# led_controller.net
KiCad netlist of a schematic drawn in EAGLE
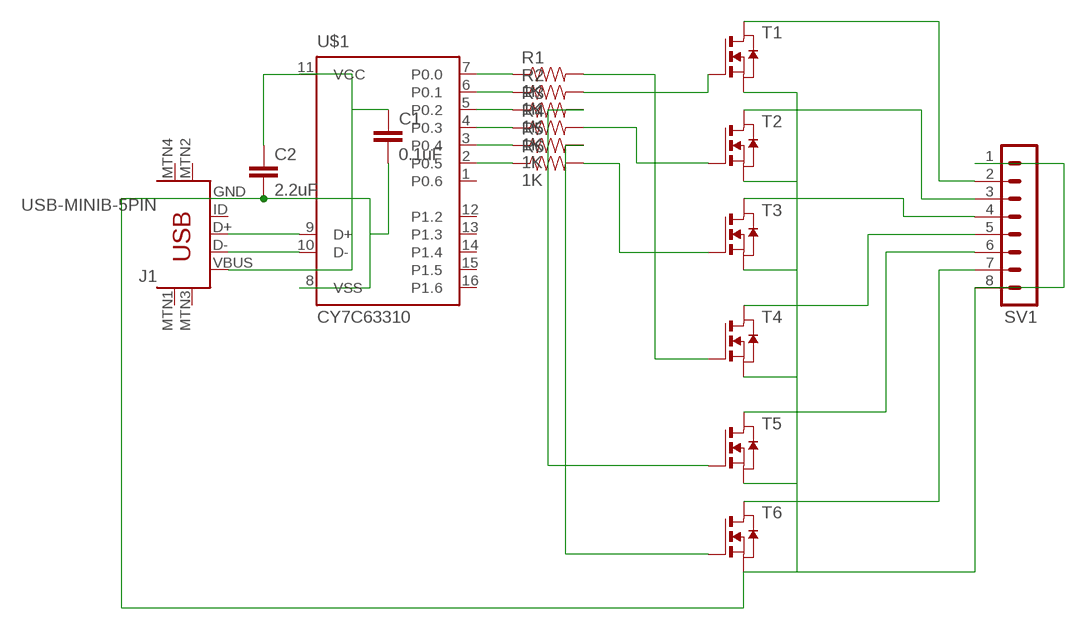
[diagram p0: schematic, sheet 1]

(export (version "E")
  (design (tool "Eeschema 10.0.6"))
  (components
    (comp (ref "C1")
      (value "0.1uF")
      (footprint "eagle-import:0603-CAP")
      (libsource (lib "eagle-import") (part "0.1UF-25V-5%(0603)"))
    )
    (comp (ref "C2")
      (value "2.2uF")
      (footprint "eagle-import:0805-CAP")
      (libsource (lib "eagle-import") (part "2.2UF-25V-+80/-20(0805)"))
    )
    (comp (ref "J1")
      (value "USB-MINIB-5PIN")
      (footprint "eagle-import:USB-MINIB")
      (libsource (lib "eagle-import") (part "USB-MINIB-5PIN"))
    )
    (comp (ref "R1")
      (value "1K")
      (footprint "eagle-import:0603-RES")
      (libsource (lib "eagle-import") (part "1KOHM-1/10W-1%(0603)"))
    )
    (comp (ref "R2")
      (value "1K")
      (footprint "eagle-import:0603-RES")
      (libsource (lib "eagle-import") (part "1KOHM-1/10W-1%(0603)"))
    )
    (comp (ref "R3")
      (value "1K")
      (footprint "eagle-import:0603-RES")
      (libsource (lib "eagle-import") (part "1KOHM-1/10W-1%(0603)"))
    )
    (comp (ref "R4")
      (value "1K")
      (footprint "eagle-import:0603-RES")
      (libsource (lib "eagle-import") (part "1KOHM-1/10W-1%(0603)"))
    )
    (comp (ref "R5")
      (value "1K")
      (footprint "eagle-import:0603-RES")
      (libsource (lib "eagle-import") (part "1KOHM-1/10W-1%(0603)"))
    )
    (comp (ref "R6")
      (value "1K")
      (footprint "eagle-import:0603-RES")
      (libsource (lib "eagle-import") (part "1KOHM-1/10W-1%(0603)"))
    )
    (comp (ref "SV1")
      (value "MA08-1")
      (footprint "eagle-import:MA08-1")
      (libsource (lib "eagle-import") (part "MA08-1"))
    )
    (comp (ref "T1")
      (value "NMOSSOT223")
      (footprint "eagle-import:SOT223")
      (libsource (lib "eagle-import") (part "NMOSSOT223"))
    )
    (comp (ref "T2")
      (value "NMOSSOT223")
      (footprint "eagle-import:SOT223")
      (libsource (lib "eagle-import") (part "NMOSSOT223"))
    )
    (comp (ref "T3")
      (value "NMOSSOT223")
      (footprint "eagle-import:SOT223")
      (libsource (lib "eagle-import") (part "NMOSSOT223"))
    )
    (comp (ref "T4")
      (value "NMOSSOT223")
      (footprint "eagle-import:SOT223")
      (libsource (lib "eagle-import") (part "NMOSSOT223"))
    )
    (comp (ref "T5")
      (value "NMOSSOT223")
      (footprint "eagle-import:SOT223")
      (libsource (lib "eagle-import") (part "NMOSSOT223"))
    )
    (comp (ref "T6")
      (value "NMOSSOT223")
      (footprint "eagle-import:SOT223")
      (libsource (lib "eagle-import") (part "NMOSSOT223"))
    )
    (comp (ref "U$1")
      (value "CY7C63310")
      (footprint "eagle-import:SOIC16")
      (libsource (lib "eagle-import") (part "CY7C63310"))
    )
  )
  (nets
    (net (code "1") (name "Net-(SV1-Pad2)") (class "Default")
      (node (ref "SV1") (pin "2") (pinfunction "2_2") (pintype "passive"))
      (node (ref "T1") (pin "2") (pinfunction "D_2") (pintype "passive"))
      (node (ref "T1") (pin "4") (pinfunction "D_4") (pintype "passive"))
    )
    (net (code "2") (name "Net-(SV1-Pad3)") (class "Default")
      (node (ref "SV1") (pin "3") (pinfunction "3_3") (pintype "passive"))
      (node (ref "T2") (pin "2") (pinfunction "D_2") (pintype "passive"))
      (node (ref "T2") (pin "4") (pinfunction "D_4") (pintype "passive"))
    )
    (net (code "3") (name "Net-(SV1-Pad4)") (class "Default")
      (node (ref "SV1") (pin "4") (pinfunction "4_4") (pintype "passive"))
      (node (ref "T3") (pin "2") (pinfunction "D_2") (pintype "passive"))
      (node (ref "T3") (pin "4") (pinfunction "D_4") (pintype "passive"))
    )
    (net (code "4") (name "Net-(SV1-Pad5)") (class "Default")
      (node (ref "SV1") (pin "5") (pinfunction "5_5") (pintype "passive"))
      (node (ref "T4") (pin "2") (pinfunction "D_2") (pintype "passive"))
      (node (ref "T4") (pin "4") (pinfunction "D_4") (pintype "passive"))
    )
    (net (code "5") (name "Net-(SV1-Pad6)") (class "Default")
      (node (ref "SV1") (pin "6") (pinfunction "6_6") (pintype "passive"))
      (node (ref "T5") (pin "2") (pinfunction "D_2") (pintype "passive"))
      (node (ref "T5") (pin "4") (pinfunction "D_4") (pintype "passive"))
    )
    (net (code "6") (name "Net-(SV1-Pad7)") (class "Default")
      (node (ref "SV1") (pin "7") (pinfunction "7_7") (pintype "passive"))
      (node (ref "T6") (pin "2") (pinfunction "D_2") (pintype "passive"))
      (node (ref "T6") (pin "4") (pinfunction "D_4") (pintype "passive"))
    )
    (net (code "7") (name "Net-(T1-G)") (class "Default")
      (node (ref "R2") (pin "2") (pinfunction "2_2") (pintype "passive"))
      (node (ref "T1") (pin "1") (pinfunction "G_1") (pintype "passive"))
    )
    (net (code "8") (name "Net-(T1-S)") (class "Default")
      (node (ref "C1") (pin "2") (pinfunction "2_2") (pintype "passive"))
      (node (ref "C2") (pin "2") (pinfunction "2_2") (pintype "passive"))
      (node (ref "J1") (pin "GND") (pinfunction "GND_GND") (pintype "bidirectional"))
      (node (ref "SV1") (pin "1") (pinfunction "1_1") (pintype "passive"))
      (node (ref "SV1") (pin "8") (pinfunction "8_8") (pintype "passive"))
      (node (ref "T1") (pin "3") (pinfunction "S_3") (pintype "passive"))
      (node (ref "T2") (pin "3") (pinfunction "S_3") (pintype "passive"))
      (node (ref "T3") (pin "3") (pinfunction "S_3") (pintype "passive"))
      (node (ref "T4") (pin "3") (pinfunction "S_3") (pintype "passive"))
      (node (ref "T5") (pin "3") (pinfunction "S_3") (pintype "passive"))
      (node (ref "T6") (pin "3") (pinfunction "S_3") (pintype "passive"))
      (node (ref "U$1") (pin "8") (pinfunction "VSS_8") (pintype "power_in"))
    )
    (net (code "9") (name "Net-(T2-G)") (class "Default")
      (node (ref "R4") (pin "2") (pinfunction "2_2") (pintype "passive"))
      (node (ref "T2") (pin "1") (pinfunction "G_1") (pintype "passive"))
    )
    (net (code "10") (name "Net-(T3-G)") (class "Default")
      (node (ref "R6") (pin "2") (pinfunction "2_2") (pintype "passive"))
      (node (ref "T3") (pin "1") (pinfunction "G_1") (pintype "passive"))
    )
    (net (code "11") (name "Net-(T4-G)") (class "Default")
      (node (ref "R1") (pin "2") (pinfunction "2_2") (pintype "passive"))
      (node (ref "T4") (pin "1") (pinfunction "G_1") (pintype "passive"))
    )
    (net (code "12") (name "Net-(T5-G)") (class "Default")
      (node (ref "R3") (pin "2") (pinfunction "2_2") (pintype "passive"))
      (node (ref "T5") (pin "1") (pinfunction "G_1") (pintype "passive"))
    )
    (net (code "13") (name "Net-(T6-G)") (class "Default")
      (node (ref "R5") (pin "2") (pinfunction "2_2") (pintype "passive"))
      (node (ref "T6") (pin "1") (pinfunction "G_1") (pintype "passive"))
    )
    (net (code "14") (name "Net-(U$1-D+)") (class "Default")
      (node (ref "J1") (pin "D+") (pinfunction "D+_D+") (pintype "bidirectional"))
      (node (ref "U$1") (pin "9") (pinfunction "D+_9") (pintype "bidirectional"))
    )
    (net (code "15") (name "Net-(U$1-D-)") (class "Default")
      (node (ref "J1") (pin "D-") (pinfunction "D-_D-") (pintype "bidirectional"))
      (node (ref "U$1") (pin "10") (pinfunction "D-_10") (pintype "bidirectional"))
    )
    (net (code "16") (name "Net-(U$1-P0.0)") (class "Default")
      (node (ref "R1") (pin "1") (pinfunction "1_1") (pintype "passive"))
      (node (ref "U$1") (pin "7") (pinfunction "P0.0_7") (pintype "bidirectional"))
    )
    (net (code "17") (name "Net-(U$1-P0.1)") (class "Default")
      (node (ref "R2") (pin "1") (pinfunction "1_1") (pintype "passive"))
      (node (ref "U$1") (pin "6") (pinfunction "P0.1_6") (pintype "bidirectional"))
    )
    (net (code "18") (name "Net-(U$1-P0.2)") (class "Default")
      (node (ref "R3") (pin "1") (pinfunction "1_1") (pintype "passive"))
      (node (ref "U$1") (pin "5") (pinfunction "P0.2_5") (pintype "bidirectional"))
    )
    (net (code "19") (name "Net-(U$1-P0.3)") (class "Default")
      (node (ref "R4") (pin "1") (pinfunction "1_1") (pintype "passive"))
      (node (ref "U$1") (pin "4") (pinfunction "P0.3_4") (pintype "bidirectional"))
    )
    (net (code "20") (name "Net-(U$1-P0.4)") (class "Default")
      (node (ref "R5") (pin "1") (pinfunction "1_1") (pintype "passive"))
      (node (ref "U$1") (pin "3") (pinfunction "P0.4_3") (pintype "bidirectional"))
    )
    (net (code "21") (name "Net-(U$1-P0.5)") (class "Default")
      (node (ref "R6") (pin "1") (pinfunction "1_1") (pintype "passive"))
      (node (ref "U$1") (pin "2") (pinfunction "P0.5_2") (pintype "bidirectional"))
    )
    (net (code "22") (name "Net-(U$1-VCC)") (class "Default")
      (node (ref "C1") (pin "1") (pinfunction "1_1") (pintype "passive"))
      (node (ref "C2") (pin "1") (pinfunction "1_1") (pintype "passive"))
      (node (ref "J1") (pin "VBUS") (pinfunction "VBUS_VBUS") (pintype "bidirectional"))
      (node (ref "U$1") (pin "11") (pinfunction "VCC_11") (pintype "power_in"))
    )
    (net (code "23") (name "unconnected-(J1-MTN1-PadMTN3)") (class "Default")
      (node (ref "J1") (pin "MTN3") (pinfunction "MTN1_MTN3") (pintype "bidirectional"))
    )
    (net (code "24") (name "unconnected-(J1-MTN2-PadMTN1)") (class "Default")
      (node (ref "J1") (pin "MTN1") (pinfunction "MTN2_MTN1") (pintype "bidirectional"))
    )
    (net (code "25") (name "unconnected-(J1-MTN3-PadMTN2)") (class "Default")
      (node (ref "J1") (pin "MTN2") (pinfunction "MTN3_MTN2") (pintype "bidirectional"))
    )
    (net (code "26") (name "unconnected-(J1-PadID)") (class "Default")
      (node (ref "J1") (pin "ID") (pinfunction "ID_ID") (pintype "bidirectional"))
    )
    (net (code "27") (name "unconnected-(J1-PadMTN4)") (class "Default")
      (node (ref "J1") (pin "MTN4") (pinfunction "MTN4_MTN4") (pintype "bidirectional"))
    )
    (net (code "28") (name "unconnected-(U$1-P0.6-Pad1)") (class "Default")
      (node (ref "U$1") (pin "1") (pinfunction "P0.6_1") (pintype "bidirectional"))
    )
    (net (code "29") (name "unconnected-(U$1-P1.2-Pad12)") (class "Default")
      (node (ref "U$1") (pin "12") (pinfunction "P1.2_12") (pintype "bidirectional"))
    )
    (net (code "30") (name "unconnected-(U$1-P1.3-Pad13)") (class "Default")
      (node (ref "U$1") (pin "13") (pinfunction "P1.3_13") (pintype "bidirectional"))
    )
    (net (code "31") (name "unconnected-(U$1-P1.4-Pad14)") (class "Default")
      (node (ref "U$1") (pin "14") (pinfunction "P1.4_14") (pintype "bidirectional"))
    )
    (net (code "32") (name "unconnected-(U$1-P1.5-Pad15)") (class "Default")
      (node (ref "U$1") (pin "15") (pinfunction "P1.5_15") (pintype "bidirectional"))
    )
    (net (code "33") (name "unconnected-(U$1-P1.6-Pad16)") (class "Default")
      (node (ref "U$1") (pin "16") (pinfunction "P1.6_16") (pintype "bidirectional"))
    )
  )
)
